# Serial-Basic-CH340C-and-USBC.net
KiCad netlist of a schematic drawn in EAGLE
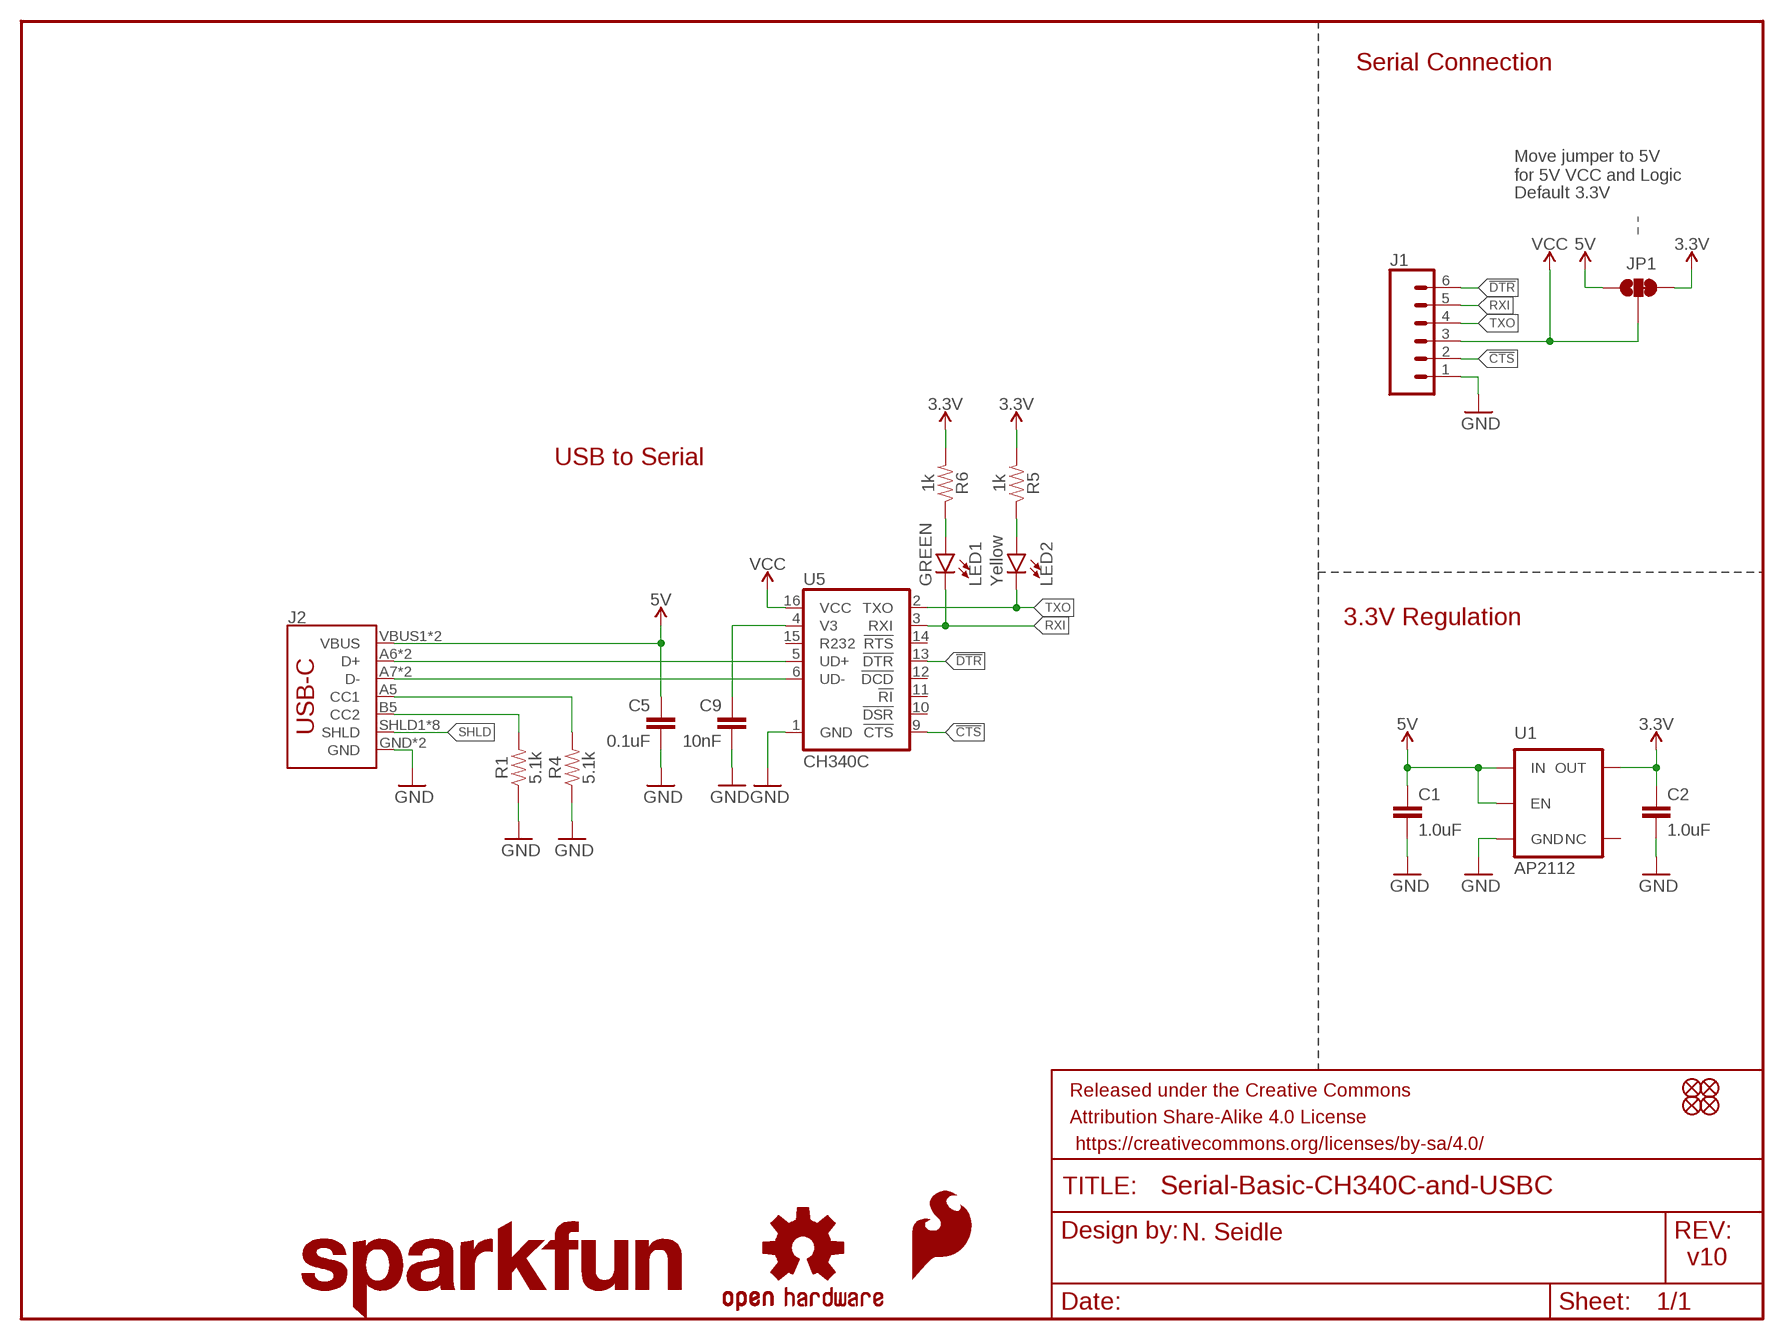
[diagram p0: schematic, sheet 1]

(export (version "E")
  (design (tool "Eeschema 10.0.6"))
  (components
    (comp (ref "C1")
      (value "1.0uF")
      (footprint "eagle-import:0603")
      (libsource (lib "eagle-import") (part "1.0UF-0603-16V-10%"))
    )
    (comp (ref "C2")
      (value "1.0uF")
      (footprint "eagle-import:0603")
      (libsource (lib "eagle-import") (part "1.0UF-0603-16V-10%"))
    )
    (comp (ref "C5")
      (value "0.1uF")
      (footprint "eagle-import:0603")
      (libsource (lib "eagle-import") (part "0.1UF-0603-25V-(+80/-20%)"))
    )
    (comp (ref "C9")
      (value "10nF")
      (footprint "eagle-import:0603")
      (libsource (lib "eagle-import") (part "10NF-0603-50V-10%"))
    )
    (comp (ref "FRAME1")
      (value "FRAME-LETTER")
      (footprint "eagle-import:CREATIVE_COMMONS")
      (libsource (lib "eagle-import") (part "FRAME-LETTER"))
    )
    (comp (ref "J1")
      (value "CONN_06SMD-FEMALE-V2")
      (footprint "eagle-import:1X06-SMD-FEMALE")
      (libsource (lib "eagle-import") (part "CONN_06SMD-FEMALE-V2"))
    )
    (comp (ref "J2")
      (value "USB_C16PIN")
      (footprint "eagle-import:USB-C-16P")
      (libsource (lib "eagle-import") (part "USB_C16PIN"))
    )
    (comp (ref "JP1")
      (value "JUMPER-SMT_3_1-NC_TRACE_SILK")
      (footprint "eagle-import:SMT-JUMPER_3_1-NC_TRACE_SILK")
      (libsource (lib "eagle-import") (part "JUMPER-SMT_3_1-NC_TRACE_SILK"))
    )
    (comp (ref "JP3")
      (value "FIDUCIAL1X2")
      (footprint "eagle-import:FIDUCIAL-1X2")
      (libsource (lib "eagle-import") (part "FIDUCIAL1X2"))
    )
    (comp (ref "JP4")
      (value "FIDUCIAL1X2")
      (footprint "eagle-import:FIDUCIAL-1X2")
      (libsource (lib "eagle-import") (part "FIDUCIAL1X2"))
    )
    (comp (ref "JP5")
      (value "FIDUCIAL1X2")
      (footprint "eagle-import:FIDUCIAL-1X2")
      (libsource (lib "eagle-import") (part "FIDUCIAL1X2"))
    )
    (comp (ref "JP6")
      (value "FIDUCIAL1X2")
      (footprint "eagle-import:FIDUCIAL-1X2")
      (libsource (lib "eagle-import") (part "FIDUCIAL1X2"))
    )
    (comp (ref "LED1")
      (value "GREEN")
      (footprint "eagle-import:LED-0603")
      (libsource (lib "eagle-import") (part "LED-GREEN0603"))
    )
    (comp (ref "LED2")
      (value "Yellow")
      (footprint "eagle-import:LED-0603")
      (libsource (lib "eagle-import") (part "LED-YELLOW0603"))
    )
    (comp (ref "LOGO1")
      (value "OSHW-LOGOS")
      (footprint "eagle-import:OSHW-LOGO-S")
      (libsource (lib "eagle-import") (part "OSHW-LOGOS"))
    )
    (comp (ref "LOGO2")
      (value "SFE_LOGO_FLAME.1_INCH")
      (footprint "eagle-import:SFE_LOGO_FLAME_.1")
      (libsource (lib "eagle-import") (part "SFE_LOGO_FLAME.1_INCH"))
    )
    (comp (ref "LOGO3")
      (value "SFE_LOGO_NAME.1_INCH")
      (footprint "eagle-import:SFE_LOGO_NAME_.1")
      (libsource (lib "eagle-import") (part "SFE_LOGO_NAME.1_INCH"))
    )
    (comp (ref "R1")
      (value "5.1k")
      (footprint "eagle-import:0603")
      (libsource (lib "eagle-import") (part "5.1KOHM5.1KOHM-0603-1/10W-1%"))
    )
    (comp (ref "R4")
      (value "5.1k")
      (footprint "eagle-import:0603")
      (libsource (lib "eagle-import") (part "5.1KOHM5.1KOHM-0603-1/10W-1%"))
    )
    (comp (ref "R5")
      (value "1k")
      (footprint "eagle-import:0603")
      (libsource (lib "eagle-import") (part "1KOHM-0603-1/10W-1%"))
    )
    (comp (ref "R6")
      (value "1k")
      (footprint "eagle-import:0603")
      (libsource (lib "eagle-import") (part "1KOHM-0603-1/10W-1%"))
    )
    (comp (ref "U1")
      (value "3.3V")
      (footprint "eagle-import:SOT23-5")
      (libsource (lib "eagle-import") (part "V_REG_AP2112K-3.3V"))
    )
    (comp (ref "U5")
      (value "CH340C")
      (footprint "eagle-import:SO016")
      (libsource (lib "eagle-import") (part "CH340C"))
    )
  )
  (nets
    (net (code "1") (name "/~{CTS}") (class "Default")
      (node (ref "J1") (pin "2") (pinfunction "2_2") (pintype "passive"))
      (node (ref "U5") (pin "9") (pinfunction "~{CTS}_9") (pintype "bidirectional"))
    )
    (net (code "2") (name "/~{DTR}") (class "Default")
      (node (ref "J1") (pin "6") (pinfunction "6_6") (pintype "passive"))
      (node (ref "U5") (pin "13") (pinfunction "~{DTR}_13") (pintype "bidirectional"))
    )
    (net (code "3") (name "3.3V") (class "Default")
      (node (ref "C2") (pin "1") (pinfunction "1_1") (pintype "passive"))
      (node (ref "JP1") (pin "3") (pinfunction "3_3") (pintype "passive"))
      (node (ref "R5") (pin "2") (pinfunction "2_2") (pintype "passive"))
      (node (ref "R6") (pin "2") (pinfunction "2_2") (pintype "passive"))
      (node (ref "U1") (pin "5") (pinfunction "OUT_5") (pintype "passive"))
    )
    (net (code "4") (name "5V") (class "Default")
      (node (ref "C1") (pin "1") (pinfunction "1_1") (pintype "passive"))
      (node (ref "C5") (pin "1") (pinfunction "1_1") (pintype "passive"))
      (node (ref "J2") (pin "VBUS1") (pinfunction "VBUS_VBUS1") (pintype "bidirectional"))
      (node (ref "J2") (pin "VBUS2") (pinfunction "VBUS_VBUS2") (pintype "bidirectional"))
      (node (ref "JP1") (pin "1") (pinfunction "1_1") (pintype "passive"))
      (node (ref "U1") (pin "1") (pinfunction "IN_1") (pintype "input"))
      (node (ref "U1") (pin "3") (pinfunction "EN_3") (pintype "input"))
    )
    (net (code "5") (name "GND") (class "Default")
      (node (ref "C1") (pin "2") (pinfunction "2_2") (pintype "passive"))
      (node (ref "C2") (pin "2") (pinfunction "2_2") (pintype "passive"))
      (node (ref "C5") (pin "2") (pinfunction "2_2") (pintype "passive"))
      (node (ref "C9") (pin "2") (pinfunction "2_2") (pintype "passive"))
      (node (ref "J1") (pin "1") (pinfunction "1_1") (pintype "passive"))
      (node (ref "J2") (pin "GND") (pinfunction "GND_GND") (pintype "bidirectional"))
      (node (ref "J2") (pin "GND2") (pinfunction "GND_GND2") (pintype "bidirectional"))
      (node (ref "R1") (pin "1") (pinfunction "1_1") (pintype "passive"))
      (node (ref "R4") (pin "1") (pinfunction "1_1") (pintype "passive"))
      (node (ref "U1") (pin "2") (pinfunction "GND_2") (pintype "input"))
      (node (ref "U5") (pin "1") (pinfunction "GND_1") (pintype "bidirectional"))
    )
    (net (code "6") (name "Net-(J2-CC1)") (class "Default")
      (node (ref "J2") (pin "A5") (pinfunction "CC1_A5") (pintype "bidirectional"))
      (node (ref "R4") (pin "2") (pinfunction "2_2") (pintype "passive"))
    )
    (net (code "7") (name "Net-(J2-CC2)") (class "Default")
      (node (ref "J2") (pin "B5") (pinfunction "CC2_B5") (pintype "bidirectional"))
      (node (ref "R1") (pin "2") (pinfunction "2_2") (pintype "passive"))
    )
    (net (code "8") (name "Net-(LED1-PadA)") (class "Default")
      (node (ref "LED1") (pin "A") (pinfunction "A_A") (pintype "passive"))
      (node (ref "R6") (pin "1") (pinfunction "1_1") (pintype "passive"))
    )
    (net (code "9") (name "Net-(LED2-PadA)") (class "Default")
      (node (ref "LED2") (pin "A") (pinfunction "A_A") (pintype "passive"))
      (node (ref "R5") (pin "1") (pinfunction "1_1") (pintype "passive"))
    )
    (net (code "10") (name "Net-(U5-UD+)") (class "Default")
      (node (ref "J2") (pin "A6") (pinfunction "D+_A6") (pintype "bidirectional"))
      (node (ref "J2") (pin "B6") (pinfunction "D+_B6") (pintype "bidirectional"))
      (node (ref "U5") (pin "5") (pinfunction "UD+_5") (pintype "bidirectional"))
    )
    (net (code "11") (name "Net-(U5-UD-)") (class "Default")
      (node (ref "J2") (pin "A7") (pinfunction "D-_A7") (pintype "bidirectional"))
      (node (ref "J2") (pin "B7") (pinfunction "D-_B7") (pintype "bidirectional"))
      (node (ref "U5") (pin "6") (pinfunction "UD-_6") (pintype "bidirectional"))
    )
    (net (code "12") (name "Net-(U5-V3)") (class "Default")
      (node (ref "C9") (pin "1") (pinfunction "1_1") (pintype "passive"))
      (node (ref "U5") (pin "4") (pinfunction "V3_4") (pintype "bidirectional"))
    )
    (net (code "13") (name "RXI") (class "Default")
      (node (ref "J1") (pin "5") (pinfunction "5_5") (pintype "passive"))
      (node (ref "LED1") (pin "C") (pinfunction "C_C") (pintype "passive"))
      (node (ref "U5") (pin "3") (pinfunction "RXI_3") (pintype "bidirectional"))
    )
    (net (code "14") (name "SHLD") (class "Default")
      (node (ref "J2") (pin "SHLD1") (pinfunction "SHLD_SHLD1") (pintype "bidirectional"))
      (node (ref "J2") (pin "SHLD2") (pinfunction "SHLD_SHLD2") (pintype "bidirectional"))
      (node (ref "J2") (pin "SHLD3") (pinfunction "SHLD_SHLD3") (pintype "bidirectional"))
      (node (ref "J2") (pin "SHLD4") (pinfunction "SHLD_SHLD4") (pintype "bidirectional"))
      (node (ref "J2") (pin "SHLD5") (pinfunction "SHLD_SHLD5") (pintype "bidirectional"))
      (node (ref "J2") (pin "SHLD6") (pinfunction "SHLD_SHLD6") (pintype "bidirectional"))
      (node (ref "J2") (pin "SHLD7") (pinfunction "SHLD_SHLD7") (pintype "bidirectional"))
      (node (ref "J2") (pin "SHLD8") (pinfunction "SHLD_SHLD8") (pintype "bidirectional"))
    )
    (net (code "15") (name "TXO") (class "Default")
      (node (ref "J1") (pin "4") (pinfunction "4_4") (pintype "passive"))
      (node (ref "LED2") (pin "C") (pinfunction "C_C") (pintype "passive"))
      (node (ref "U5") (pin "2") (pinfunction "TXO_2") (pintype "bidirectional"))
    )
    (net (code "16") (name "VCC") (class "Default")
      (node (ref "J1") (pin "3") (pinfunction "3_3") (pintype "passive"))
      (node (ref "JP1") (pin "2") (pinfunction "2_2") (pintype "passive"))
      (node (ref "U5") (pin "16") (pinfunction "VCC_16") (pintype "bidirectional"))
    )
    (net (code "17") (name "unconnected-(U1-NC-Pad4)") (class "Default")
      (node (ref "U1") (pin "4") (pinfunction "NC_4") (pintype "no_connect"))
    )
    (net (code "18") (name "unconnected-(U5-R232-Pad15)") (class "Default")
      (node (ref "U5") (pin "15") (pinfunction "R232_15") (pintype "bidirectional"))
    )
    (net (code "19") (name "unconnected-(U5-~{DCD}-Pad12)") (class "Default")
      (node (ref "U5") (pin "12") (pinfunction "~{DCD}_12") (pintype "bidirectional"))
    )
    (net (code "20") (name "unconnected-(U5-~{DSR}-Pad10)") (class "Default")
      (node (ref "U5") (pin "10") (pinfunction "~{DSR}_10") (pintype "bidirectional"))
    )
    (net (code "21") (name "unconnected-(U5-~{RI}-Pad11)") (class "Default")
      (node (ref "U5") (pin "11") (pinfunction "~{RI}_11") (pintype "bidirectional"))
    )
    (net (code "22") (name "unconnected-(U5-~{RTS}-Pad14)") (class "Default")
      (node (ref "U5") (pin "14") (pinfunction "~{RTS}_14") (pintype "bidirectional"))
    )
  )
)
